# asomator4.net
KiCad netlist of a schematic drawn in EAGLE
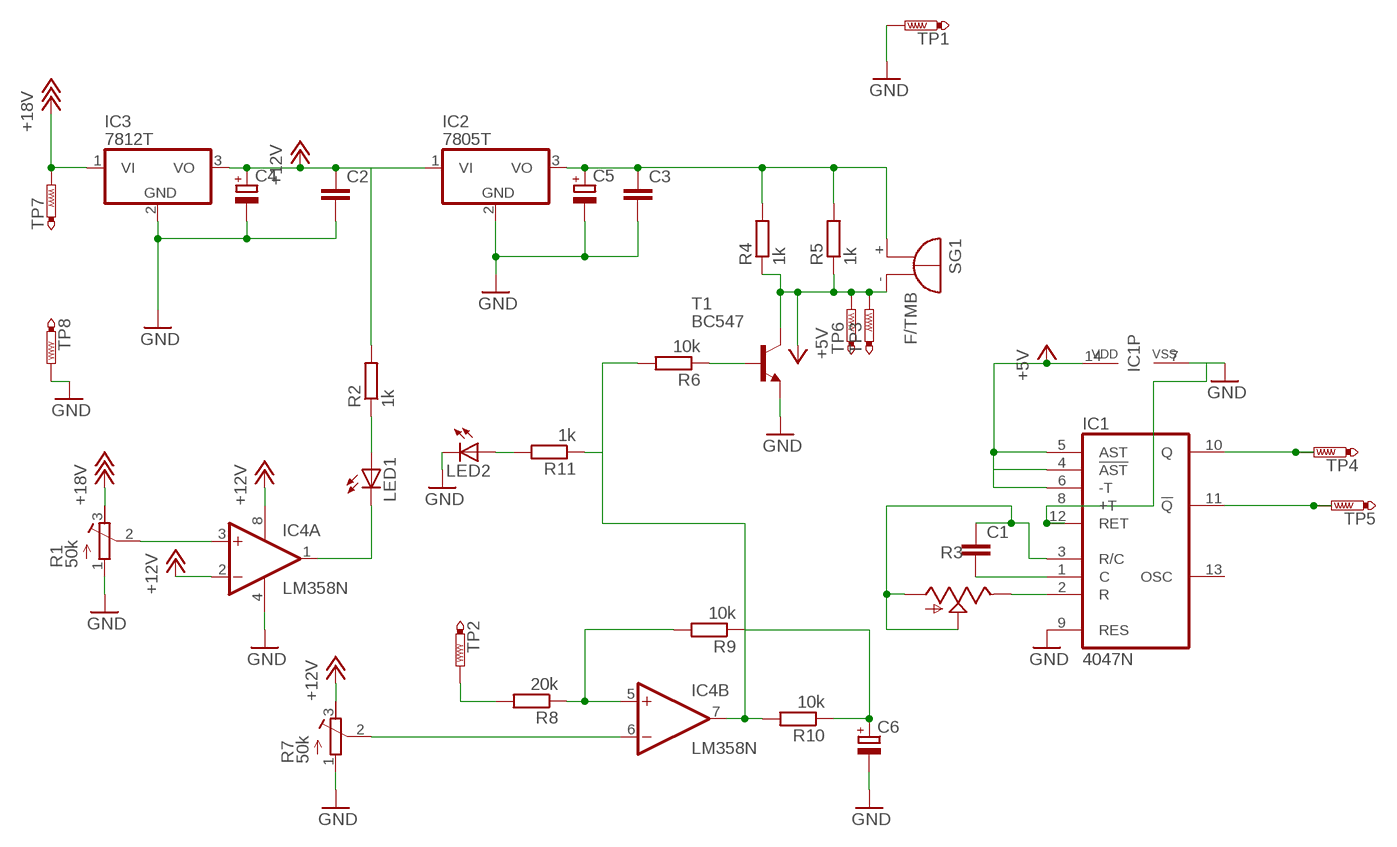
[diagram p0: schematic, sheet 1]

(export (version "E")
  (design (tool "Eeschema 10.0.6"))
  (components
    (comp (ref "C1")
      (value "C-EU025-030X050")
      (footprint "eagle-import:C025-030X050")
      (libsource (lib "eagle-import") (part "C-EU025-030X050"))
    )
    (comp (ref "C2")
      (value "C-EU025-030X050")
      (footprint "eagle-import:C025-030X050")
      (libsource (lib "eagle-import") (part "C-EU025-030X050"))
    )
    (comp (ref "C3")
      (value "C-EU025-030X050")
      (footprint "eagle-import:C025-030X050")
      (libsource (lib "eagle-import") (part "C-EU025-030X050"))
    )
    (comp (ref "C4")
      (value "CPOL-EUE2.5-6")
      (footprint "eagle-import:E2,5-6")
      (libsource (lib "eagle-import") (part "CPOL-EUE2.5-6"))
    )
    (comp (ref "C5")
      (value "CPOL-EUE2.5-6")
      (footprint "eagle-import:E2,5-6")
      (libsource (lib "eagle-import") (part "CPOL-EUE2.5-6"))
    )
    (comp (ref "C6")
      (value "CPOL-EUE2.5-6")
      (footprint "eagle-import:E2,5-6")
      (libsource (lib "eagle-import") (part "CPOL-EUE2.5-6"))
    )
    (comp (ref "IC1")
      (value "4047N")
      (footprint "eagle-import:DIL14")
      (libsource (lib "eagle-import") (part "4047N"))
    )
    (comp (ref "IC2")
      (value "7805T")
      (footprint "eagle-import:TO220H")
      (libsource (lib "eagle-import") (part "78T05"))
    )
    (comp (ref "IC3")
      (value "7812T")
      (footprint "eagle-import:TO220H")
      (libsource (lib "eagle-import") (part "78T12"))
    )
    (comp (ref "IC4")
      (value "LM358N")
      (footprint "eagle-import:DIL08")
      (libsource (lib "eagle-import") (part "LM358N"))
    )
    (comp (ref "LED1")
      (value "LED5MM")
      (footprint "eagle-import:LED5MM")
      (libsource (lib "eagle-import") (part "LED5MM"))
    )
    (comp (ref "LED2")
      (value "LED5MM")
      (footprint "eagle-import:LED5MM")
      (libsource (lib "eagle-import") (part "LED5MM"))
    )
    (comp (ref "R1")
      (value "50k")
      (footprint "eagle-import:RTRIM64W")
      (libsource (lib "eagle-import") (part "R-TRIMM64W"))
    )
    (comp (ref "R2")
      (value "1k")
      (footprint "eagle-import:0207_10")
      (libsource (lib "eagle-import") (part "R-EU_0207/10"))
    )
    (comp (ref "R3")
      (value "TRIM_US-CA9V")
      (footprint "eagle-import:CA9V")
      (libsource (lib "eagle-import") (part "TRIM_US-CA9V"))
    )
    (comp (ref "R4")
      (value "1k")
      (footprint "eagle-import:0207_10")
      (libsource (lib "eagle-import") (part "R-EU_0207/10"))
    )
    (comp (ref "R5")
      (value "1k")
      (footprint "eagle-import:0207_10")
      (libsource (lib "eagle-import") (part "R-EU_0207/10"))
    )
    (comp (ref "R6")
      (value "10k")
      (footprint "eagle-import:0207_10")
      (libsource (lib "eagle-import") (part "R-EU_0207/10"))
    )
    (comp (ref "R7")
      (value "50k")
      (footprint "eagle-import:RTRIM64W")
      (libsource (lib "eagle-import") (part "R-TRIMM64W"))
    )
    (comp (ref "R8")
      (value "20k")
      (footprint "eagle-import:0207_10")
      (libsource (lib "eagle-import") (part "R-EU_0207/10"))
    )
    (comp (ref "R9")
      (value "10k")
      (footprint "eagle-import:0207_10")
      (libsource (lib "eagle-import") (part "R-EU_0207/10"))
    )
    (comp (ref "R10")
      (value "10k")
      (footprint "eagle-import:0207_10")
      (libsource (lib "eagle-import") (part "R-EU_0207/10"))
    )
    (comp (ref "R11")
      (value "1k")
      (footprint "eagle-import:0207_10")
      (libsource (lib "eagle-import") (part "R-EU_0207/10"))
    )
    (comp (ref "SG1")
      (value "F/TMB")
      (footprint "eagle-import:F_TMB")
      (libsource (lib "eagle-import") (part "F/TMB"))
    )
    (comp (ref "T1")
      (value "BC547")
      (footprint "eagle-import:TO92")
      (libsource (lib "eagle-import") (part "BC547"))
    )
    (comp (ref "TP1")
      (value "PTR1PAD1-13Y")
      (footprint "eagle-import:P1-13Y")
      (libsource (lib "eagle-import") (part "PTR1PAD1-13Y"))
    )
    (comp (ref "TP2")
      (value "PTR1PAD1-13Y")
      (footprint "eagle-import:P1-13Y")
      (libsource (lib "eagle-import") (part "PTR1PAD1-13Y"))
    )
    (comp (ref "TP3")
      (value "PTR1PAD1-13Y")
      (footprint "eagle-import:P1-13Y")
      (libsource (lib "eagle-import") (part "PTR1PAD1-13Y"))
    )
    (comp (ref "TP4")
      (value "PTR1PAD1-13Y")
      (footprint "eagle-import:P1-13Y")
      (libsource (lib "eagle-import") (part "PTR1PAD1-13Y"))
    )
    (comp (ref "TP5")
      (value "PTR1PAD1-13Y")
      (footprint "eagle-import:P1-13Y")
      (libsource (lib "eagle-import") (part "PTR1PAD1-13Y"))
    )
    (comp (ref "TP6")
      (value "PTR1PAD1-13Y")
      (footprint "eagle-import:P1-13Y")
      (libsource (lib "eagle-import") (part "PTR1PAD1-13Y"))
    )
    (comp (ref "TP7")
      (value "PTR1PAD1-13Y")
      (footprint "eagle-import:P1-13Y")
      (libsource (lib "eagle-import") (part "PTR1PAD1-13Y"))
    )
    (comp (ref "TP8")
      (value "PTR1PAD1-13Y")
      (footprint "eagle-import:P1-13Y")
      (libsource (lib "eagle-import") (part "PTR1PAD1-13Y"))
    )
  )
  (nets
    (net (code "1") (name "+5V") (class "Default")
      (node (ref "IC1") (pin "14") (pinfunction "VDD_14") (pintype "power_in"))
      (node (ref "IC1") (pin "4") (pinfunction "~{AST}_4") (pintype "input"))
      (node (ref "IC1") (pin "5") (pinfunction "AST_5") (pintype "input"))
      (node (ref "IC1") (pin "6") (pinfunction "-T_6") (pintype "input"))
      (node (ref "R4") (pin "1") (pinfunction "1_1") (pintype "passive"))
      (node (ref "R5") (pin "1") (pinfunction "1_1") (pintype "passive"))
      (node (ref "SG1") (pin "-") (pinfunction "-_-") (pintype "passive"))
      (node (ref "T1") (pin "3") (pinfunction "C_3") (pintype "passive"))
      (node (ref "TP3") (pin "TP") (pinfunction "TP_TP") (pintype "input"))
      (node (ref "TP6") (pin "TP") (pinfunction "TP_TP") (pintype "input"))
    )
    (net (code "2") (name "+12V") (class "Default")
      (node (ref "C2") (pin "1") (pinfunction "1_1") (pintype "passive"))
      (node (ref "C4") (pin "+") (pinfunction "+_+") (pintype "passive"))
      (node (ref "IC2") (pin "1") (pinfunction "VI_1") (pintype "input"))
      (node (ref "IC3") (pin "3") (pinfunction "VO_3") (pintype "passive"))
      (node (ref "IC4") (pin "2") (pinfunction "-IN_2") (pintype "input"))
      (node (ref "IC4") (pin "8") (pinfunction "V+_8") (pintype "power_in"))
      (node (ref "R2") (pin "2") (pinfunction "2_2") (pintype "passive"))
      (node (ref "R7") (pin "3") (pinfunction "E_3") (pintype "passive"))
    )
    (net (code "3") (name "+18V") (class "Default")
      (node (ref "IC3") (pin "1") (pinfunction "VI_1") (pintype "input"))
      (node (ref "R1") (pin "3") (pinfunction "E_3") (pintype "passive"))
      (node (ref "TP7") (pin "TP") (pinfunction "TP_TP") (pintype "input"))
    )
    (net (code "4") (name "GND") (class "Default")
      (node (ref "C2") (pin "2") (pinfunction "2_2") (pintype "passive"))
      (node (ref "C3") (pin "2") (pinfunction "2_2") (pintype "passive"))
      (node (ref "C4") (pin "-") (pinfunction "-_-") (pintype "passive"))
      (node (ref "C5") (pin "-") (pinfunction "-_-") (pintype "passive"))
      (node (ref "C6") (pin "-") (pinfunction "-_-") (pintype "passive"))
      (node (ref "IC1") (pin "12") (pinfunction "RET_12") (pintype "input"))
      (node (ref "IC1") (pin "7") (pinfunction "VSS_7") (pintype "power_in"))
      (node (ref "IC1") (pin "8") (pinfunction "+T_8") (pintype "input"))
      (node (ref "IC1") (pin "9") (pinfunction "RES_9") (pintype "input"))
      (node (ref "IC2") (pin "2") (pinfunction "GND_2") (pintype "passive"))
      (node (ref "IC3") (pin "2") (pinfunction "GND_2") (pintype "passive"))
      (node (ref "IC4") (pin "4") (pinfunction "V-_4") (pintype "power_in"))
      (node (ref "LED2") (pin "K") (pinfunction "C_K") (pintype "passive"))
      (node (ref "R1") (pin "1") (pinfunction "A_1") (pintype "passive"))
      (node (ref "R7") (pin "1") (pinfunction "A_1") (pintype "passive"))
      (node (ref "T1") (pin "1") (pinfunction "E_1") (pintype "passive"))
      (node (ref "TP1") (pin "TP") (pinfunction "TP_TP") (pintype "input"))
      (node (ref "TP8") (pin "TP") (pinfunction "TP_TP") (pintype "input"))
    )
    (net (code "5") (name "Net-(C6-Pad+)") (class "Default")
      (node (ref "C6") (pin "+") (pinfunction "+_+") (pintype "passive"))
      (node (ref "R10") (pin "1") (pinfunction "1_1") (pintype "passive"))
      (node (ref "R9") (pin "1") (pinfunction "1_1") (pintype "passive"))
    )
    (net (code "6") (name "Net-(IC1A-C)") (class "Default")
      (node (ref "C1") (pin "2") (pinfunction "2_2") (pintype "passive"))
      (node (ref "IC1") (pin "1") (pinfunction "C_1") (pintype "input"))
    )
    (net (code "7") (name "Net-(IC1A-Q)") (class "Default")
      (node (ref "IC1") (pin "10") (pinfunction "Q_10") (pintype "output"))
      (node (ref "TP4") (pin "TP") (pinfunction "TP_TP") (pintype "input"))
    )
    (net (code "8") (name "Net-(IC1A-R)") (class "Default")
      (node (ref "IC1") (pin "2") (pinfunction "R_2") (pintype "input"))
      (node (ref "R3") (pin "E") (pinfunction "E_E") (pintype "passive"))
    )
    (net (code "9") (name "Net-(IC1A-R{slash}C)") (class "Default")
      (node (ref "C1") (pin "1") (pinfunction "1_1") (pintype "passive"))
      (node (ref "IC1") (pin "3") (pinfunction "R/C_3") (pintype "input"))
      (node (ref "R3") (pin "A") (pinfunction "A_A") (pintype "passive"))
      (node (ref "R3") (pin "S") (pinfunction "S_S") (pintype "passive"))
    )
    (net (code "10") (name "Net-(IC1A-~{Q})") (class "Default")
      (node (ref "IC1") (pin "11") (pinfunction "~{Q}_11") (pintype "output"))
      (node (ref "TP5") (pin "TP") (pinfunction "TP_TP") (pintype "input"))
    )
    (net (code "11") (name "Net-(IC2-VO)") (class "Default")
      (node (ref "C3") (pin "1") (pinfunction "1_1") (pintype "passive"))
      (node (ref "C5") (pin "+") (pinfunction "+_+") (pintype "passive"))
      (node (ref "IC2") (pin "3") (pinfunction "VO_3") (pintype "passive"))
      (node (ref "R4") (pin "2") (pinfunction "2_2") (pintype "passive"))
      (node (ref "R5") (pin "2") (pinfunction "2_2") (pintype "passive"))
      (node (ref "SG1") (pin "+") (pinfunction "+_+") (pintype "passive"))
    )
    (net (code "12") (name "Net-(IC4A-+IN)") (class "Default")
      (node (ref "IC4") (pin "3") (pinfunction "+IN_3") (pintype "input"))
      (node (ref "R1") (pin "2") (pinfunction "S_2") (pintype "passive"))
    )
    (net (code "13") (name "Net-(IC4A-OUT)") (class "Default")
      (node (ref "IC4") (pin "1") (pinfunction "OUT_1") (pintype "output"))
      (node (ref "LED1") (pin "K") (pinfunction "C_K") (pintype "passive"))
    )
    (net (code "14") (name "Net-(IC4B-+IN)") (class "Default")
      (node (ref "IC4") (pin "5") (pinfunction "+IN_5") (pintype "input"))
      (node (ref "R8") (pin "1") (pinfunction "1_1") (pintype "passive"))
      (node (ref "R9") (pin "2") (pinfunction "2_2") (pintype "passive"))
    )
    (net (code "15") (name "Net-(IC4B--IN)") (class "Default")
      (node (ref "IC4") (pin "6") (pinfunction "-IN_6") (pintype "input"))
      (node (ref "R7") (pin "2") (pinfunction "S_2") (pintype "passive"))
    )
    (net (code "16") (name "Net-(IC4B-OUT)") (class "Default")
      (node (ref "IC4") (pin "7") (pinfunction "OUT_7") (pintype "output"))
      (node (ref "R10") (pin "2") (pinfunction "2_2") (pintype "passive"))
      (node (ref "R11") (pin "1") (pinfunction "1_1") (pintype "passive"))
      (node (ref "R6") (pin "2") (pinfunction "2_2") (pintype "passive"))
    )
    (net (code "17") (name "Net-(LED1-PadA)") (class "Default")
      (node (ref "LED1") (pin "A") (pinfunction "A_A") (pintype "passive"))
      (node (ref "R2") (pin "1") (pinfunction "1_1") (pintype "passive"))
    )
    (net (code "18") (name "Net-(LED2-PadA)") (class "Default")
      (node (ref "LED2") (pin "A") (pinfunction "A_A") (pintype "passive"))
      (node (ref "R11") (pin "2") (pinfunction "2_2") (pintype "passive"))
    )
    (net (code "19") (name "Net-(R8-Pad2)") (class "Default")
      (node (ref "R8") (pin "2") (pinfunction "2_2") (pintype "passive"))
      (node (ref "TP2") (pin "TP") (pinfunction "TP_TP") (pintype "input"))
    )
    (net (code "20") (name "Net-(T1-B)") (class "Default")
      (node (ref "R6") (pin "1") (pinfunction "1_1") (pintype "passive"))
      (node (ref "T1") (pin "2") (pinfunction "B_2") (pintype "passive"))
    )
    (net (code "21") (name "unconnected-(IC1A-OSC-Pad13)") (class "Default")
      (node (ref "IC1") (pin "13") (pinfunction "OSC_13") (pintype "output"))
    )
  )
)
